# AccessControl.net
KiCad netlist of a schematic drawn in EAGLE
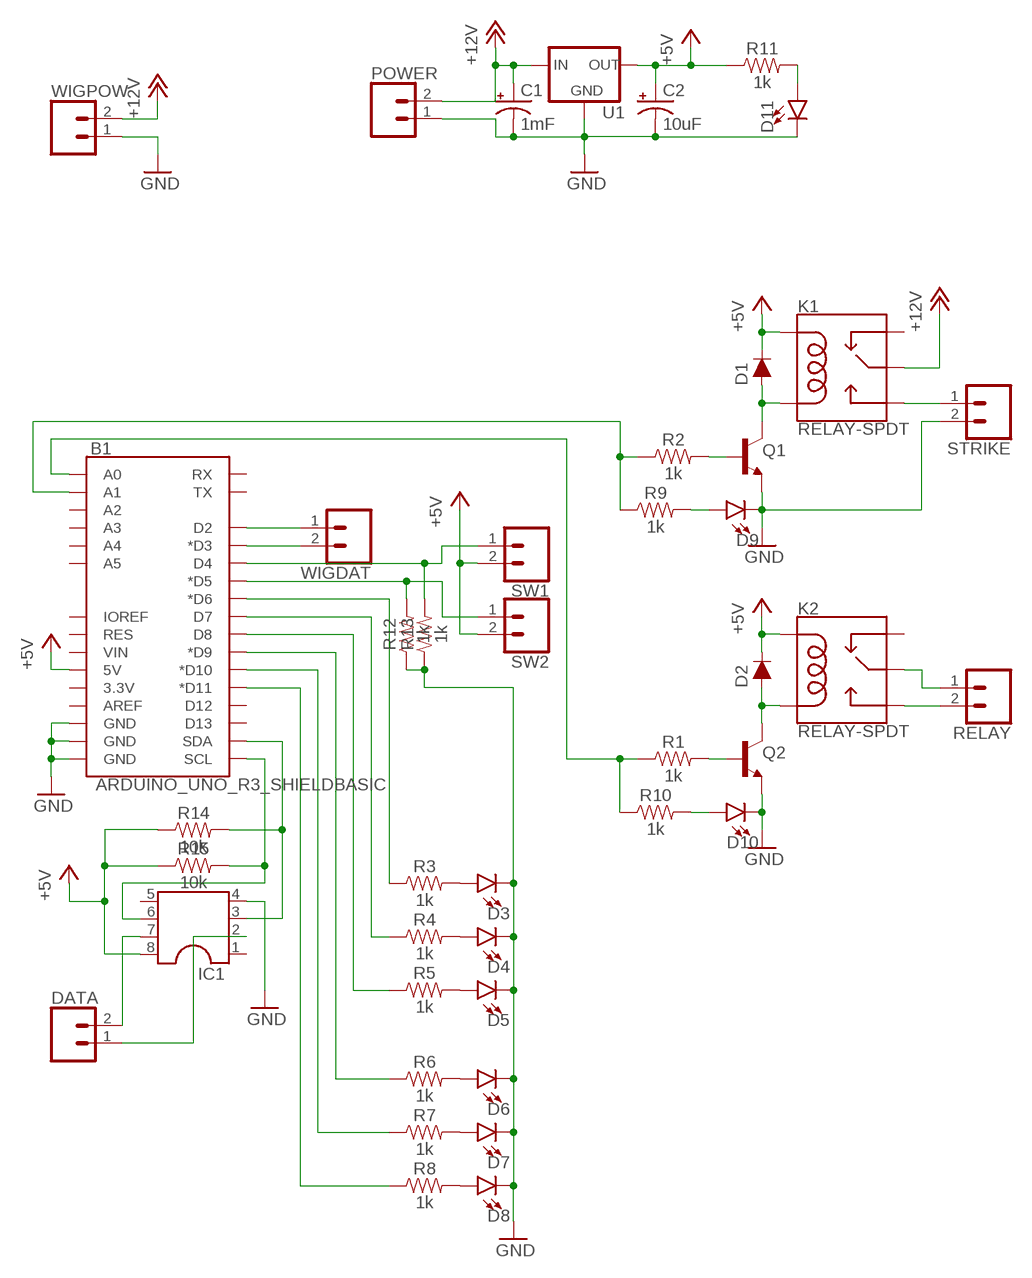
[diagram p0: schematic, sheet 1]

(export (version "E")
  (design (tool "Eeschema 10.0.6"))
  (components
    (comp (ref "B1")
      (value "ARDUINO_UNO_R3_SHIELDBASIC")
      (footprint "eagle-import:UNO_R3_SHIELD")
      (libsource (lib "eagle-import") (part "ARDUINO_UNO_R3_SHIELDBASIC"))
    )
    (comp (ref "C1")
      (value "1mF")
      (footprint "eagle-import:CPOL-RADIAL-5MM-10MM")
      (libsource (lib "eagle-import") (part "1000UF-RADIAL-5MM-25V-20%"))
    )
    (comp (ref "C2")
      (value "10uF")
      (footprint "eagle-import:CPOL-RADIAL-2.5MM-5MM")
      (libsource (lib "eagle-import") (part "10UF-POLAR-RADIAL-2.5MM-25V-20%"))
    )
    (comp (ref "D1")
      (value "DIODE-KIT2")
      (footprint "eagle-import:DIODE-1N4001-KIT")
      (libsource (lib "eagle-import") (part "DIODE-KIT2"))
    )
    (comp (ref "D2")
      (value "DIODE-KIT2")
      (footprint "eagle-import:DIODE-1N4001-KIT")
      (libsource (lib "eagle-import") (part "DIODE-KIT2"))
    )
    (comp (ref "D3")
      (value "LED5MM")
      (footprint "eagle-import:LED_5MM")
      (libsource (lib "eagle-import") (part "LED5MM"))
    )
    (comp (ref "D4")
      (value "LED5MM")
      (footprint "eagle-import:LED_5MM")
      (libsource (lib "eagle-import") (part "LED5MM"))
    )
    (comp (ref "D5")
      (value "LED5MM")
      (footprint "eagle-import:LED_5MM")
      (libsource (lib "eagle-import") (part "LED5MM"))
    )
    (comp (ref "D6")
      (value "LED5MM")
      (footprint "eagle-import:LED_5MM")
      (libsource (lib "eagle-import") (part "LED5MM"))
    )
    (comp (ref "D7")
      (value "LED5MM")
      (footprint "eagle-import:LED_5MM")
      (libsource (lib "eagle-import") (part "LED5MM"))
    )
    (comp (ref "D8")
      (value "LED5MM")
      (footprint "eagle-import:LED_5MM")
      (libsource (lib "eagle-import") (part "LED5MM"))
    )
    (comp (ref "D9")
      (value "LED5MM")
      (footprint "eagle-import:LED_5MM")
      (libsource (lib "eagle-import") (part "LED5MM"))
    )
    (comp (ref "D10")
      (value "LED5MM")
      (footprint "eagle-import:LED_5MM")
      (libsource (lib "eagle-import") (part "LED5MM"))
    )
    (comp (ref "D11")
      (value "LED5MM")
      (footprint "eagle-import:LED_5MM")
      (libsource (lib "eagle-import") (part "LED5MM"))
    )
    (comp (ref "DATA")
      (value "CONN_025MM")
      (footprint "eagle-import:SCREWTERMINAL-5MM-2")
      (libsource (lib "eagle-import") (part "CONN_025MM"))
    )
    (comp (ref "IC1")
      (value "DIL8")
      (footprint "eagle-import:DIL08")
      (libsource (lib "eagle-import") (part "DIL8"))
    )
    (comp (ref "K1")
      (value "RELAY-SPDT")
      (footprint "eagle-import:RELAY-JZC")
      (libsource (lib "eagle-import") (part "RELAY-SPDT-JZC-11F"))
    )
    (comp (ref "K2")
      (value "RELAY-SPDT")
      (footprint "eagle-import:RELAY-JZC")
      (libsource (lib "eagle-import") (part "RELAY-SPDT-JZC-11F"))
    )
    (comp (ref "POWER")
      (value "CONN_025MM")
      (footprint "eagle-import:SCREWTERMINAL-5MM-2")
      (libsource (lib "eagle-import") (part "CONN_025MM"))
    )
    (comp (ref "Q1")
      (value "TRANS_NPN-P2N2222A")
      (footprint "eagle-import:TO-92")
      (libsource (lib "eagle-import") (part "TRANS_NPN-P2N2222A"))
    )
    (comp (ref "Q2")
      (value "TRANS_NPN-P2N2222A")
      (footprint "eagle-import:TO-92")
      (libsource (lib "eagle-import") (part "TRANS_NPN-P2N2222A"))
    )
    (comp (ref "R1")
      (value "1k")
      (footprint "eagle-import:AXIAL-0.1")
      (libsource (lib "eagle-import") (part "1KOHM-VERT-1/6W-5%"))
    )
    (comp (ref "R2")
      (value "1k")
      (footprint "eagle-import:AXIAL-0.1")
      (libsource (lib "eagle-import") (part "1KOHM-VERT-1/6W-5%"))
    )
    (comp (ref "R3")
      (value "1k")
      (footprint "eagle-import:AXIAL-0.1")
      (libsource (lib "eagle-import") (part "1KOHM-VERT-1/6W-5%"))
    )
    (comp (ref "R4")
      (value "1k")
      (footprint "eagle-import:AXIAL-0.1")
      (libsource (lib "eagle-import") (part "1KOHM-VERT-1/6W-5%"))
    )
    (comp (ref "R5")
      (value "1k")
      (footprint "eagle-import:AXIAL-0.1")
      (libsource (lib "eagle-import") (part "1KOHM-VERT-1/6W-5%"))
    )
    (comp (ref "R6")
      (value "1k")
      (footprint "eagle-import:AXIAL-0.1")
      (libsource (lib "eagle-import") (part "1KOHM-VERT-1/6W-5%"))
    )
    (comp (ref "R7")
      (value "1k")
      (footprint "eagle-import:AXIAL-0.1")
      (libsource (lib "eagle-import") (part "1KOHM-VERT-1/6W-5%"))
    )
    (comp (ref "R8")
      (value "1k")
      (footprint "eagle-import:AXIAL-0.1")
      (libsource (lib "eagle-import") (part "1KOHM-VERT-1/6W-5%"))
    )
    (comp (ref "R9")
      (value "1k")
      (footprint "eagle-import:AXIAL-0.1")
      (libsource (lib "eagle-import") (part "1KOHM-VERT-1/6W-5%"))
    )
    (comp (ref "R10")
      (value "1k")
      (footprint "eagle-import:AXIAL-0.1")
      (libsource (lib "eagle-import") (part "1KOHM-VERT-1/6W-5%"))
    )
    (comp (ref "R11")
      (value "1k")
      (footprint "eagle-import:AXIAL-0.1")
      (libsource (lib "eagle-import") (part "1KOHM-VERT-1/6W-5%"))
    )
    (comp (ref "R12")
      (value "1k")
      (footprint "eagle-import:AXIAL-0.1")
      (libsource (lib "eagle-import") (part "1KOHM-VERT-1/6W-5%"))
    )
    (comp (ref "R13")
      (value "1k")
      (footprint "eagle-import:AXIAL-0.1")
      (libsource (lib "eagle-import") (part "1KOHM-VERT-1/6W-5%"))
    )
    (comp (ref "R14")
      (value "10k")
      (footprint "eagle-import:AXIAL-0.1")
      (libsource (lib "eagle-import") (part "10KOHM-VERT-1/6W-5%"))
    )
    (comp (ref "R15")
      (value "10k")
      (footprint "eagle-import:AXIAL-0.1")
      (libsource (lib "eagle-import") (part "10KOHM-VERT-1/6W-5%"))
    )
    (comp (ref "RELAY")
      (value "CONN_025MM")
      (footprint "eagle-import:SCREWTERMINAL-5MM-2")
      (libsource (lib "eagle-import") (part "CONN_025MM"))
    )
    (comp (ref "STRIKE")
      (value "CONN_025MM")
      (footprint "eagle-import:SCREWTERMINAL-5MM-2")
      (libsource (lib "eagle-import") (part "CONN_025MM"))
    )
    (comp (ref "SW1")
      (value "CONN_025MM")
      (footprint "eagle-import:SCREWTERMINAL-5MM-2")
      (libsource (lib "eagle-import") (part "CONN_025MM"))
    )
    (comp (ref "SW2")
      (value "CONN_025MM")
      (footprint "eagle-import:SCREWTERMINAL-5MM-2")
      (libsource (lib "eagle-import") (part "CONN_025MM"))
    )
    (comp (ref "U1")
      (value "V_REG_78XXSINK")
      (footprint "eagle-import:TO220-IGO")
      (libsource (lib "eagle-import") (part "V_REG_78XXSINK"))
    )
    (comp (ref "WIGDAT")
      (value "CONN_025MM")
      (footprint "eagle-import:SCREWTERMINAL-5MM-2")
      (libsource (lib "eagle-import") (part "CONN_025MM"))
    )
    (comp (ref "WIGPOW")
      (value "CONN_025MM")
      (footprint "eagle-import:SCREWTERMINAL-5MM-2")
      (libsource (lib "eagle-import") (part "CONN_025MM"))
    )
  )
  (nets
    (net (code "1") (name "+5V") (class "Default")
      (node (ref "B1") (pin "5V") (pinfunction "5V_5V") (pintype "bidirectional"))
      (node (ref "C2") (pin "1") (pinfunction "+_1") (pintype "passive"))
      (node (ref "D1") (pin "C") (pinfunction "C_C") (pintype "passive"))
      (node (ref "D2") (pin "C") (pinfunction "C_C") (pintype "passive"))
      (node (ref "IC1") (pin "8") (pinfunction "8_8") (pintype "passive"))
      (node (ref "K1") (pin "5") (pinfunction "COIL1_5") (pintype "bidirectional"))
      (node (ref "K2") (pin "5") (pinfunction "COIL1_5") (pintype "bidirectional"))
      (node (ref "R11") (pin "P$1") (pinfunction "1_P$1") (pintype "passive"))
      (node (ref "R14") (pin "P$1") (pinfunction "1_P$1") (pintype "passive"))
      (node (ref "R15") (pin "P$1") (pinfunction "1_P$1") (pintype "passive"))
      (node (ref "SW1") (pin "2") (pinfunction "2_2") (pintype "passive"))
      (node (ref "SW2") (pin "2") (pinfunction "2_2") (pintype "passive"))
      (node (ref "U1") (pin "OUT") (pinfunction "OUT_OUT") (pintype "passive"))
    )
    (net (code "2") (name "+12V") (class "Default")
      (node (ref "C1") (pin "+") (pinfunction "+_+") (pintype "passive"))
      (node (ref "K1") (pin "4") (pinfunction "MAIN_4") (pintype "bidirectional"))
      (node (ref "POWER") (pin "2") (pinfunction "2_2") (pintype "passive"))
      (node (ref "U1") (pin "IN") (pinfunction "IN_IN") (pintype "input"))
      (node (ref "WIGPOW") (pin "2") (pinfunction "2_2") (pintype "passive"))
    )
    (net (code "3") (name "GND") (class "Default")
      (node (ref "B1") (pin "GND@0") (pinfunction "GND_GND@0") (pintype "bidirectional"))
      (node (ref "B1") (pin "GND@1") (pinfunction "GND_GND@1") (pintype "bidirectional"))
      (node (ref "B1") (pin "GND@2") (pinfunction "GND_GND@2") (pintype "bidirectional"))
      (node (ref "C1") (pin "-") (pinfunction "-_-") (pintype "passive"))
      (node (ref "C2") (pin "2") (pinfunction "-_2") (pintype "passive"))
      (node (ref "D10") (pin "K") (pinfunction "C_K") (pintype "passive"))
      (node (ref "D11") (pin "K") (pinfunction "C_K") (pintype "passive"))
      (node (ref "D3") (pin "K") (pinfunction "C_K") (pintype "passive"))
      (node (ref "D4") (pin "K") (pinfunction "C_K") (pintype "passive"))
      (node (ref "D5") (pin "K") (pinfunction "C_K") (pintype "passive"))
      (node (ref "D6") (pin "K") (pinfunction "C_K") (pintype "passive"))
      (node (ref "D7") (pin "K") (pinfunction "C_K") (pintype "passive"))
      (node (ref "D8") (pin "K") (pinfunction "C_K") (pintype "passive"))
      (node (ref "D9") (pin "K") (pinfunction "C_K") (pintype "passive"))
      (node (ref "IC1") (pin "4") (pinfunction "4_4") (pintype "passive"))
      (node (ref "POWER") (pin "1") (pinfunction "1_1") (pintype "passive"))
      (node (ref "Q1") (pin "3") (pinfunction "E_3") (pintype "passive"))
      (node (ref "Q2") (pin "3") (pinfunction "E_3") (pintype "passive"))
      (node (ref "R12") (pin "P$1") (pinfunction "1_P$1") (pintype "passive"))
      (node (ref "R13") (pin "P$1") (pinfunction "1_P$1") (pintype "passive"))
      (node (ref "STRIKE") (pin "2") (pinfunction "2_2") (pintype "passive"))
      (node (ref "U1") (pin "GND") (pinfunction "GND_GND") (pintype "input"))
      (node (ref "WIGPOW") (pin "1") (pinfunction "1_1") (pintype "passive"))
    )
    (net (code "4") (name "Net-(B1-*D3)") (class "Default")
      (node (ref "B1") (pin "D3") (pinfunction "*D3_D3") (pintype "bidirectional"))
      (node (ref "WIGDAT") (pin "2") (pinfunction "2_2") (pintype "passive"))
    )
    (net (code "5") (name "Net-(B1-*D5)") (class "Default")
      (node (ref "B1") (pin "D5") (pinfunction "*D5_D5") (pintype "bidirectional"))
      (node (ref "R12") (pin "P$2") (pinfunction "2_P$2") (pintype "passive"))
      (node (ref "SW2") (pin "1") (pinfunction "1_1") (pintype "passive"))
    )
    (net (code "6") (name "Net-(B1-*D6)") (class "Default")
      (node (ref "B1") (pin "D6") (pinfunction "*D6_D6") (pintype "bidirectional"))
      (node (ref "R3") (pin "P$1") (pinfunction "1_P$1") (pintype "passive"))
    )
    (net (code "7") (name "Net-(B1-*D9)") (class "Default")
      (node (ref "B1") (pin "D9") (pinfunction "*D9_D9") (pintype "bidirectional"))
      (node (ref "R6") (pin "P$1") (pinfunction "1_P$1") (pintype "passive"))
    )
    (net (code "8") (name "Net-(B1-*D10)") (class "Default")
      (node (ref "B1") (pin "D10") (pinfunction "*D10_D10") (pintype "bidirectional"))
      (node (ref "R7") (pin "P$1") (pinfunction "1_P$1") (pintype "passive"))
    )
    (net (code "9") (name "Net-(B1-*D11)") (class "Default")
      (node (ref "B1") (pin "D11") (pinfunction "*D11_D11") (pintype "bidirectional"))
      (node (ref "R8") (pin "P$1") (pinfunction "1_P$1") (pintype "passive"))
    )
    (net (code "10") (name "Net-(B1-PadD2)") (class "Default")
      (node (ref "B1") (pin "D2") (pinfunction "D2_D2") (pintype "bidirectional"))
      (node (ref "WIGDAT") (pin "1") (pinfunction "1_1") (pintype "passive"))
    )
    (net (code "11") (name "Net-(DATA-Pad1)") (class "Default")
      (node (ref "DATA") (pin "1") (pinfunction "1_1") (pintype "passive"))
      (node (ref "IC1") (pin "2") (pinfunction "2_2") (pintype "passive"))
    )
    (net (code "12") (name "Net-(DATA-Pad2)") (class "Default")
      (node (ref "DATA") (pin "2") (pinfunction "2_2") (pintype "passive"))
      (node (ref "IC1") (pin "7") (pinfunction "7_7") (pintype "passive"))
    )
    (net (code "13") (name "Net-(K1-COIL2)") (class "Default")
      (node (ref "D1") (pin "A") (pinfunction "A_A") (pintype "passive"))
      (node (ref "K1") (pin "1") (pinfunction "COIL2_1") (pintype "bidirectional"))
      (node (ref "Q1") (pin "1") (pinfunction "C_1") (pintype "passive"))
    )
    (net (code "14") (name "Net-(K1-NO)") (class "Default")
      (node (ref "K1") (pin "3") (pinfunction "NO_3") (pintype "bidirectional"))
      (node (ref "STRIKE") (pin "1") (pinfunction "1_1") (pintype "passive"))
    )
    (net (code "15") (name "Net-(K2-COIL2)") (class "Default")
      (node (ref "D2") (pin "A") (pinfunction "A_A") (pintype "passive"))
      (node (ref "K2") (pin "1") (pinfunction "COIL2_1") (pintype "bidirectional"))
      (node (ref "Q2") (pin "1") (pinfunction "C_1") (pintype "passive"))
    )
    (net (code "16") (name "Net-(K2-MAIN)") (class "Default")
      (node (ref "K2") (pin "4") (pinfunction "MAIN_4") (pintype "bidirectional"))
      (node (ref "RELAY") (pin "1") (pinfunction "1_1") (pintype "passive"))
    )
    (net (code "17") (name "Net-(K2-NO)") (class "Default")
      (node (ref "K2") (pin "3") (pinfunction "NO_3") (pintype "bidirectional"))
      (node (ref "RELAY") (pin "2") (pinfunction "2_2") (pintype "passive"))
    )
    (net (code "18") (name "Net-(Q1-B)") (class "Default")
      (node (ref "Q1") (pin "2") (pinfunction "B_2") (pintype "passive"))
      (node (ref "R2") (pin "P$2") (pinfunction "2_P$2") (pintype "passive"))
    )
    (net (code "19") (name "Net-(Q2-B)") (class "Default")
      (node (ref "Q2") (pin "2") (pinfunction "B_2") (pintype "passive"))
      (node (ref "R1") (pin "P$2") (pinfunction "2_P$2") (pintype "passive"))
    )
    (net (code "20") (name "Net-(R1-1)") (class "Default")
      (node (ref "B1") (pin "A0") (pinfunction "A0_A0") (pintype "bidirectional"))
      (node (ref "R1") (pin "P$1") (pinfunction "1_P$1") (pintype "passive"))
      (node (ref "R10") (pin "P$1") (pinfunction "1_P$1") (pintype "passive"))
    )
    (net (code "21") (name "Net-(R2-1)") (class "Default")
      (node (ref "B1") (pin "A1") (pinfunction "A1_A1") (pintype "bidirectional"))
      (node (ref "R2") (pin "P$1") (pinfunction "1_P$1") (pintype "passive"))
      (node (ref "R9") (pin "P$1") (pinfunction "1_P$1") (pintype "passive"))
    )
    (net (code "22") (name "Net-(R3-2)") (class "Default")
      (node (ref "D3") (pin "A") (pinfunction "A_A") (pintype "passive"))
      (node (ref "R3") (pin "P$2") (pinfunction "2_P$2") (pintype "passive"))
    )
    (net (code "23") (name "Net-(R4-1)") (class "Default")
      (node (ref "B1") (pin "D7") (pinfunction "D7_D7") (pintype "bidirectional"))
      (node (ref "R4") (pin "P$1") (pinfunction "1_P$1") (pintype "passive"))
    )
    (net (code "24") (name "Net-(R4-2)") (class "Default")
      (node (ref "D4") (pin "A") (pinfunction "A_A") (pintype "passive"))
      (node (ref "R4") (pin "P$2") (pinfunction "2_P$2") (pintype "passive"))
    )
    (net (code "25") (name "Net-(R5-1)") (class "Default")
      (node (ref "B1") (pin "D8") (pinfunction "D8_D8") (pintype "bidirectional"))
      (node (ref "R5") (pin "P$1") (pinfunction "1_P$1") (pintype "passive"))
    )
    (net (code "26") (name "Net-(R5-2)") (class "Default")
      (node (ref "D5") (pin "A") (pinfunction "A_A") (pintype "passive"))
      (node (ref "R5") (pin "P$2") (pinfunction "2_P$2") (pintype "passive"))
    )
    (net (code "27") (name "Net-(R6-2)") (class "Default")
      (node (ref "D6") (pin "A") (pinfunction "A_A") (pintype "passive"))
      (node (ref "R6") (pin "P$2") (pinfunction "2_P$2") (pintype "passive"))
    )
    (net (code "28") (name "Net-(R7-2)") (class "Default")
      (node (ref "D7") (pin "A") (pinfunction "A_A") (pintype "passive"))
      (node (ref "R7") (pin "P$2") (pinfunction "2_P$2") (pintype "passive"))
    )
    (net (code "29") (name "Net-(R8-2)") (class "Default")
      (node (ref "D8") (pin "A") (pinfunction "A_A") (pintype "passive"))
      (node (ref "R8") (pin "P$2") (pinfunction "2_P$2") (pintype "passive"))
    )
    (net (code "30") (name "Net-(R9-2)") (class "Default")
      (node (ref "D9") (pin "A") (pinfunction "A_A") (pintype "passive"))
      (node (ref "R9") (pin "P$2") (pinfunction "2_P$2") (pintype "passive"))
    )
    (net (code "31") (name "Net-(R10-2)") (class "Default")
      (node (ref "D10") (pin "A") (pinfunction "A_A") (pintype "passive"))
      (node (ref "R10") (pin "P$2") (pinfunction "2_P$2") (pintype "passive"))
    )
    (net (code "32") (name "Net-(R11-2)") (class "Default")
      (node (ref "D11") (pin "A") (pinfunction "A_A") (pintype "passive"))
      (node (ref "R11") (pin "P$2") (pinfunction "2_P$2") (pintype "passive"))
    )
    (net (code "33") (name "Net-(R13-2)") (class "Default")
      (node (ref "B1") (pin "D4") (pinfunction "D4_D4") (pintype "bidirectional"))
      (node (ref "R13") (pin "P$2") (pinfunction "2_P$2") (pintype "passive"))
      (node (ref "SW1") (pin "1") (pinfunction "1_1") (pintype "passive"))
    )
    (net (code "34") (name "Net-(R14-2)") (class "Default")
      (node (ref "B1") (pin "SDA") (pinfunction "SDA_SDA") (pintype "bidirectional"))
      (node (ref "IC1") (pin "3") (pinfunction "3_3") (pintype "passive"))
      (node (ref "R14") (pin "P$2") (pinfunction "2_P$2") (pintype "passive"))
    )
    (net (code "35") (name "Net-(R15-2)") (class "Default")
      (node (ref "B1") (pin "SCL") (pinfunction "SCL_SCL") (pintype "bidirectional"))
      (node (ref "IC1") (pin "6") (pinfunction "6_6") (pintype "passive"))
      (node (ref "R15") (pin "P$2") (pinfunction "2_P$2") (pintype "passive"))
    )
    (net (code "36") (name "unconnected-(B1-Pad3.3V)") (class "Default")
      (node (ref "B1") (pin "3.3V") (pinfunction "3.3V_3.3V") (pintype "bidirectional"))
    )
    (net (code "37") (name "unconnected-(B1-PadA2)") (class "Default")
      (node (ref "B1") (pin "A2") (pinfunction "A2_A2") (pintype "bidirectional"))
    )
    (net (code "38") (name "unconnected-(B1-PadA3)") (class "Default")
      (node (ref "B1") (pin "A3") (pinfunction "A3_A3") (pintype "bidirectional"))
    )
    (net (code "39") (name "unconnected-(B1-PadA4)") (class "Default")
      (node (ref "B1") (pin "A4") (pinfunction "A4_A4") (pintype "bidirectional"))
    )
    (net (code "40") (name "unconnected-(B1-PadA5)") (class "Default")
      (node (ref "B1") (pin "A5") (pinfunction "A5_A5") (pintype "bidirectional"))
    )
    (net (code "41") (name "unconnected-(B1-PadAREF)") (class "Default")
      (node (ref "B1") (pin "AREF") (pinfunction "AREF_AREF") (pintype "bidirectional"))
    )
    (net (code "42") (name "unconnected-(B1-PadD12)") (class "Default")
      (node (ref "B1") (pin "D12") (pinfunction "D12_D12") (pintype "bidirectional"))
    )
    (net (code "43") (name "unconnected-(B1-PadD13)") (class "Default")
      (node (ref "B1") (pin "D13") (pinfunction "D13_D13") (pintype "bidirectional"))
    )
    (net (code "44") (name "unconnected-(B1-PadIOREF)") (class "Default")
      (node (ref "B1") (pin "IOREF") (pinfunction "IOREF_IOREF") (pintype "bidirectional"))
    )
    (net (code "45") (name "unconnected-(B1-PadRES)") (class "Default")
      (node (ref "B1") (pin "RES") (pinfunction "RES_RES") (pintype "bidirectional"))
    )
    (net (code "46") (name "unconnected-(B1-PadRX)") (class "Default")
      (node (ref "B1") (pin "RX") (pinfunction "RX_RX") (pintype "bidirectional"))
    )
    (net (code "47") (name "unconnected-(B1-PadTX)") (class "Default")
      (node (ref "B1") (pin "TX") (pinfunction "TX_TX") (pintype "bidirectional"))
    )
    (net (code "48") (name "unconnected-(B1-PadVIN)") (class "Default")
      (node (ref "B1") (pin "VIN") (pinfunction "VIN_VIN") (pintype "bidirectional"))
    )
    (net (code "49") (name "unconnected-(IC1-Pad1)") (class "Default")
      (node (ref "IC1") (pin "1") (pinfunction "1_1") (pintype "passive"))
    )
    (net (code "50") (name "unconnected-(IC1-Pad5)") (class "Default")
      (node (ref "IC1") (pin "5") (pinfunction "5_5") (pintype "passive"))
    )
    (net (code "51") (name "unconnected-(K1-NC-Pad2)") (class "Default")
      (node (ref "K1") (pin "2") (pinfunction "NC_2") (pintype "bidirectional"))
    )
    (net (code "52") (name "unconnected-(K2-NC-Pad2)") (class "Default")
      (node (ref "K2") (pin "2") (pinfunction "NC_2") (pintype "bidirectional"))
    )
  )
)
